# WizBoard.net
KiCad netlist of a schematic drawn in Altium Designer
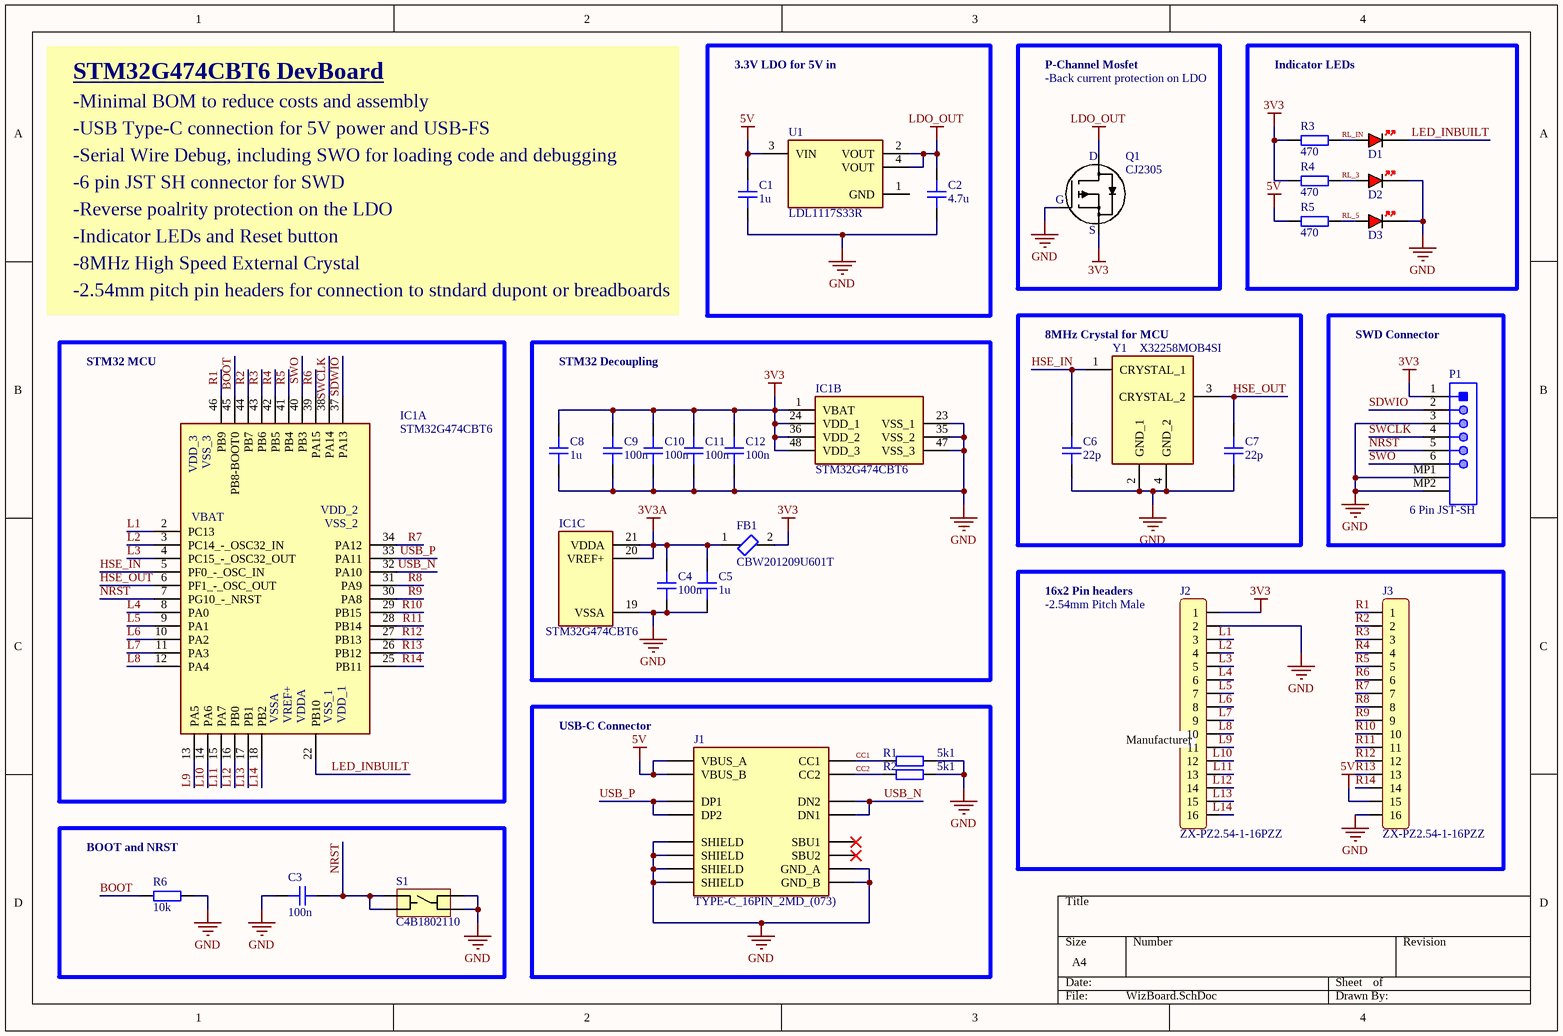
[diagram p0: WizBoard.SchDoc]

(export (version "E")
  (design (tool "Eeschema 10.0.6"))
  (components
    (comp (ref "C1")
      (value "1u")
      (footprint "CAP_0805")
      (description "Capacitor SMD 0805")
      (fields
        (field (name "MANUFACTURER") "Samsung Electro-Mechanics")
        (field (name "MANUFACTURER PART NUMBER") "CL21B105KAFNNNE")
      )
      (libsource (lib "BRye_SCHLib") (part "CAP_0805"))
    )
    (comp (ref "C2")
      (value "4.7u")
      (footprint "CAP_0805")
      (description "Capacitor SMD 0805")
      (fields
        (field (name "MANUFACTURER") "Samsung Electro-Mechanics")
        (field (name "MANUFACTURER PART NUMBER") "CL21A475KBQNNNE")
      )
      (libsource (lib "BRye_SCHLib") (part "CAP_0805"))
    )
    (comp (ref "C3")
      (value "100n")
      (footprint "CAP_0805")
      (description "Capacitor SMD 0805")
      (fields
        (field (name "MANUFACTURER") "Samsung Electro-Mechanics")
        (field (name "MANUFACTURER PART NUMBER") "CL21B104KBCNNNC")
      )
      (libsource (lib "BRye_SCHLib") (part "CAP_0805"))
    )
    (comp (ref "C4")
      (value "100n")
      (footprint "CAP_0805")
      (description "Capacitor SMD 0805")
      (fields
        (field (name "MANUFACTURER") "Samsung Electro-Mechanics")
        (field (name "MANUFACTURER PART NUMBER") "CL21B104KBCNNNC")
      )
      (libsource (lib "BRye_SCHLib") (part "CAP_0805"))
    )
    (comp (ref "C5")
      (value "1u")
      (footprint "CAP_0805")
      (description "Capacitor SMD 0805")
      (fields
        (field (name "MANUFACTURER") "Samsung Electro-Mechanics")
        (field (name "MANUFACTURER PART NUMBER") "CL21B105KAFNNNE")
      )
      (libsource (lib "BRye_SCHLib") (part "CAP_0805"))
    )
    (comp (ref "C6")
      (value "22p")
      (footprint "CAP_0805")
      (description "Capacitor SMD 0805")
      (fields
        (field (name "MANUFACTURER") "Samsung Electro-Mechanics")
        (field (name "MANUFACTURER PART NUMBER") "CL21C220JBANNNC")
      )
      (libsource (lib "BRye_SCHLib") (part "CAP_0805"))
    )
    (comp (ref "C7")
      (value "22p")
      (footprint "CAP_0805")
      (description "Capacitor SMD 0805")
      (fields
        (field (name "MANUFACTURER") "Samsung Electro-Mechanics")
        (field (name "MANUFACTURER PART NUMBER") "CL21C220JBANNNC")
      )
      (libsource (lib "BRye_SCHLib") (part "CAP_0805"))
    )
    (comp (ref "C8")
      (value "1u")
      (footprint "CAP_0805")
      (description "Capacitor SMD 0805")
      (fields
        (field (name "MANUFACTURER") "Samsung Electro-Mechanics")
        (field (name "MANUFACTURER PART NUMBER") "CL21B105KAFNNNE")
      )
      (libsource (lib "BRye_SCHLib") (part "CAP_0805"))
    )
    (comp (ref "C9")
      (value "100n")
      (footprint "CAP_0805")
      (description "Capacitor SMD 0805")
      (fields
        (field (name "MANUFACTURER") "Samsung Electro-Mechanics")
        (field (name "MANUFACTURER PART NUMBER") "CL21B104KBCNNNC")
      )
      (libsource (lib "BRye_SCHLib") (part "CAP_0805"))
    )
    (comp (ref "C10")
      (value "100n")
      (footprint "CAP_0805")
      (description "Capacitor SMD 0805")
      (fields
        (field (name "MANUFACTURER") "Samsung Electro-Mechanics")
        (field (name "MANUFACTURER PART NUMBER") "CL21B104KBCNNNC")
      )
      (libsource (lib "BRye_SCHLib") (part "CAP_0805"))
    )
    (comp (ref "C11")
      (value "100n")
      (footprint "CAP_0805")
      (description "Capacitor SMD 0805")
      (fields
        (field (name "MANUFACTURER") "Samsung Electro-Mechanics")
        (field (name "MANUFACTURER PART NUMBER") "CL21B104KBCNNNC")
      )
      (libsource (lib "BRye_SCHLib") (part "CAP_0805"))
    )
    (comp (ref "C12")
      (value "100n")
      (footprint "CAP_0805")
      (description "Capacitor SMD 0805")
      (fields
        (field (name "MANUFACTURER") "Samsung Electro-Mechanics")
        (field (name "MANUFACTURER PART NUMBER") "CL21B104KBCNNNC")
      )
      (libsource (lib "BRye_SCHLib") (part "CAP_0805"))
    )
    (comp (ref "D1")
      (value "RED")
      (footprint "LED_0805_RED")
      (description "LED 0805 RED SMD")
      (fields
        (field (name "MANUFACTURER") "XINGLIGHT")
        (field (name "MANUFACTURER PART NUMBER") "XL-2012SURC")
      )
      (libsource (lib "BRye_SCHLib") (part "LED_0805_RED"))
    )
    (comp (ref "D2")
      (value "RED")
      (footprint "LED_0805_RED")
      (description "LED 0805 RED SMD")
      (fields
        (field (name "MANUFACTURER") "XINGLIGHT")
        (field (name "MANUFACTURER PART NUMBER") "XL-2012SURC")
      )
      (libsource (lib "BRye_SCHLib") (part "LED_0805_RED"))
    )
    (comp (ref "D3")
      (value "RED")
      (footprint "LED_0805_RED")
      (description "LED 0805 RED SMD")
      (fields
        (field (name "MANUFACTURER") "XINGLIGHT")
        (field (name "MANUFACTURER PART NUMBER") "XL-2012SURC")
      )
      (libsource (lib "BRye_SCHLib") (part "LED_0805_RED"))
    )
    (comp (ref "FB1")
      (value "CBW201209U601T")
      (footprint "SamacSys:BEADC2112X105N")
      (description "Ferrite Beads 600 @ 100MHz 500mA 0805 RoHS")
      (fields (field (name "MANUFACTURER") "SUNLORD"))
      (libsource (lib "BRye_SCHLib") (part "GZ2012D601TF"))
    )
    (comp (ref "IC1")
      (value "STM32G474CBT6")
      (footprint "SamacSys:QFP50P900X900X160-48N")
      (description "Integrated Circuit")
      (fields
        (field (name "MANUFACTURER") "STMicroelectronics")
        (field (name "MANUFACTURER PART NUMBER") "STM32G474CBT6TR")
      )
      (libsource (lib "BRye_SCHLib") (part "STM32G474CBT6"))
    )
    (comp (ref "J1")
      (value "TYPE-C_16PIN_2MD_(073)")
      (footprint "SHOUHAN_TYPE-C_16PIN_2MD_(073)")
      (description "DC-5V 5A Type C USB")
      (fields
        (field (name "MANUFACTURER") "SHOU HAN")
        (field (name "MANUFACTURER PART NUMBER") "TYPE-C 16PIN 2MD(073)")
      )
      (libsource (lib "BRye_SCHLib") (part "TYPE-C_16PIN_2MD_(073)"))
    )
    (comp (ref "J2")
      (value "ZX-PZ2.54-1-16PZZ")
      (footprint "16p Pin Header")
      (fields (field (name "MANUFACTURER") "Megastar"))
      (libsource (lib "BRye_SCHLib") (part "ZX-PZ2.54-1-16PZZ"))
    )
    (comp (ref "J3")
      (value "ZX-PZ2.54-1-16PZZ")
      (footprint "16p Pin Header")
      (fields (field (name "MANUFACTURER") "Megastar"))
      (libsource (lib "BRye_SCHLib") (part "ZX-PZ2.54-1-16PZZ"))
    )
    (comp (ref "P1")
      (value "6 Pin JST-SH")
      (footprint "JST-SM06B-SRSS-TB_V")
      (description "Male Header, Pitch 1 mm, 1 x 6 Position, Height 2.95 mm, -25 to 85 degC, RoHS, Tape and Reel")
      (fields
        (field (name "MANUFACTURER") "JST")
        (field (name "MANUFACTURER PART NUMBER") "SM06B-SRSS-TB(LF)(SN)")
      )
      (libsource (lib "Altium Content Vault") (part "CN-1P-2M-R6"))
    )
    (comp (ref "Q1")
      (value "CJ2305")
      (footprint "SOT-23")
      (description "P-Channel 12V 4.1A 0.35W Surface Mount SOT-23")
      (fields (field (name "MANUFACTURER") "JSCJ"))
      (libsource (lib "BRye_SCHLib") (part "PJM10H01PSA"))
    )
    (comp (ref "R1")
      (value "5k1")
      (footprint "RES_0805")
      (description "Resistor SMD 0805")
      (fields
        (field (name "MANUFACTURER") "FOJAN")
        (field (name "MANUFACTURER PART NUMBER") "FRC0805F5101TS")
      )
      (libsource (lib "BRye_SCHLib") (part "RES_0805"))
    )
    (comp (ref "R2")
      (value "5k1")
      (footprint "RES_0805")
      (description "Resistor SMD 0805")
      (fields
        (field (name "MANUFACTURER") "FOJAN")
        (field (name "MANUFACTURER PART NUMBER") "FRC0805F5101TS")
      )
      (libsource (lib "BRye_SCHLib") (part "RES_0805"))
    )
    (comp (ref "R3")
      (value "470")
      (footprint "RES_0805")
      (description "Resistor SMD 0805")
      (fields
        (field (name "MANUFACTURER") "FOJAN")
        (field (name "MANUFACTURER PART NUMBER") "FRC0805F4700TS")
      )
      (libsource (lib "BRye_SCHLib") (part "RES_0805"))
    )
    (comp (ref "R4")
      (value "470")
      (footprint "RES_0805")
      (description "Resistor SMD 0805")
      (fields
        (field (name "MANUFACTURER") "FOJAN")
        (field (name "MANUFACTURER PART NUMBER") "FRC0805F4700TS")
      )
      (libsource (lib "BRye_SCHLib") (part "RES_0805"))
    )
    (comp (ref "R5")
      (value "470")
      (footprint "RES_0805")
      (description "Resistor SMD 0805")
      (fields
        (field (name "MANUFACTURER") "FOJAN")
        (field (name "MANUFACTURER PART NUMBER") "FRC0805F4700TS")
      )
      (libsource (lib "BRye_SCHLib") (part "RES_0805"))
    )
    (comp (ref "R6")
      (value "10k")
      (footprint "RES_0805")
      (description "Resistor SMD 0805")
      (fields
        (field (name "MANUFACTURER") "FOJAN")
        (field (name "MANUFACTURER PART NUMBER") "FRC0805F1002TS")
      )
      (libsource (lib "BRye_SCHLib") (part "RES_0805"))
    )
    (comp (ref "S1")
      (value "C4B1802110")
      (footprint "SW-SMD_4P-L3.5-W3.0-P1.50-LS4.7")
      (description "SMD NO Push Button Switch")
      (fields (field (name "MANUFACTURER") "SAMZO"))
      (libsource (lib "BRye_SCHLib") (part "C4B1802110"))
    )
    (comp (ref "U1")
      (value "LDL1117S33R")
      (footprint "SOT-223")
      (description "IC REG LINEAR 3.3V 1.2A SOT223")
      (fields (field (name "MANUFACTURER") "ST"))
      (libsource (lib "BRye_SCHLib") (part "LDL1117S33R"))
    )
    (comp (ref "Y1")
      (value "X32258MOB4SI")
      (footprint "SamacSys:X32258MOB4SI")
      (description "Crystal or Oscillator")
      (fields (field (name "MANUFACTURER") "YXC"))
      (libsource (lib "BRye_SCHLib") (part "X32258MOB4SI"))
    )
  )
  (nets
    (net (code "1") (name "/BOOT") (class "Default")
      (node (ref "IC1") (pin "45") (pinfunction "PB8-BOOT0_45") (pintype "passive"))
      (node (ref "R6") (pin "1") (pinfunction "1_1") (pintype "passive"))
    )
    (net (code "2") (name "/CC1") (class "Default")
      (node (ref "J1") (pin "A5") (pinfunction "CC1_A5") (pintype "passive"))
      (node (ref "R1") (pin "1") (pinfunction "1_1") (pintype "passive"))
    )
    (net (code "3") (name "/CC2") (class "Default")
      (node (ref "J1") (pin "B5") (pinfunction "CC2_B5") (pintype "passive"))
      (node (ref "R2") (pin "1") (pinfunction "1_1") (pintype "passive"))
    )
    (net (code "4") (name "/HSE_IN") (class "Default")
      (node (ref "C6") (pin "2") (pinfunction "2_2") (pintype "passive"))
      (node (ref "IC1") (pin "5") (pinfunction "PF0_-_OSC_IN_5") (pintype "passive"))
      (node (ref "Y1") (pin "1") (pinfunction "CRYSTAL_1_1") (pintype "passive"))
    )
    (net (code "5") (name "/HSE_OUT") (class "Default")
      (node (ref "C7") (pin "2") (pinfunction "2_2") (pintype "passive"))
      (node (ref "IC1") (pin "6") (pinfunction "PF1_-_OSC_OUT_6") (pintype "passive"))
      (node (ref "Y1") (pin "3") (pinfunction "CRYSTAL_2_3") (pintype "passive"))
    )
    (net (code "6") (name "/L1") (class "Default")
      (node (ref "IC1") (pin "2") (pinfunction "PC13_2") (pintype "passive"))
      (node (ref "J2") (pin "3") (pinfunction "3_3") (pintype "passive"))
    )
    (net (code "7") (name "/L2") (class "Default")
      (node (ref "IC1") (pin "3") (pinfunction "PC14_-_OSC32_IN_3") (pintype "passive"))
      (node (ref "J2") (pin "4") (pinfunction "4_4") (pintype "passive"))
    )
    (net (code "8") (name "/L3") (class "Default")
      (node (ref "IC1") (pin "4") (pinfunction "PC15_-_OSC32_OUT_4") (pintype "passive"))
      (node (ref "J2") (pin "5") (pinfunction "5_5") (pintype "passive"))
    )
    (net (code "9") (name "/L4") (class "Default")
      (node (ref "IC1") (pin "8") (pinfunction "PA0_8") (pintype "passive"))
      (node (ref "J2") (pin "6") (pinfunction "6_6") (pintype "passive"))
    )
    (net (code "10") (name "/L5") (class "Default")
      (node (ref "IC1") (pin "9") (pinfunction "PA1_9") (pintype "passive"))
      (node (ref "J2") (pin "7") (pinfunction "7_7") (pintype "passive"))
    )
    (net (code "11") (name "/L6") (class "Default")
      (node (ref "IC1") (pin "10") (pinfunction "PA2_10") (pintype "passive"))
      (node (ref "J2") (pin "8") (pinfunction "8_8") (pintype "passive"))
    )
    (net (code "12") (name "/L7") (class "Default")
      (node (ref "IC1") (pin "11") (pinfunction "PA3_11") (pintype "passive"))
      (node (ref "J2") (pin "9") (pinfunction "9_9") (pintype "passive"))
    )
    (net (code "13") (name "/L8") (class "Default")
      (node (ref "IC1") (pin "12") (pinfunction "PA4_12") (pintype "passive"))
      (node (ref "J2") (pin "10") (pinfunction "10_10") (pintype "passive"))
    )
    (net (code "14") (name "/L9") (class "Default")
      (node (ref "IC1") (pin "13") (pinfunction "PA5_13") (pintype "passive"))
      (node (ref "J2") (pin "11") (pinfunction "11_11") (pintype "passive"))
    )
    (net (code "15") (name "/L10") (class "Default")
      (node (ref "IC1") (pin "14") (pinfunction "PA6_14") (pintype "passive"))
      (node (ref "J2") (pin "12") (pinfunction "12_12") (pintype "passive"))
    )
    (net (code "16") (name "/L11") (class "Default")
      (node (ref "IC1") (pin "15") (pinfunction "PA7_15") (pintype "passive"))
      (node (ref "J2") (pin "13") (pinfunction "13_13") (pintype "passive"))
    )
    (net (code "17") (name "/L12") (class "Default")
      (node (ref "IC1") (pin "16") (pinfunction "PB0_16") (pintype "passive"))
      (node (ref "J2") (pin "14") (pinfunction "14_14") (pintype "passive"))
    )
    (net (code "18") (name "/L13") (class "Default")
      (node (ref "IC1") (pin "17") (pinfunction "PB1_17") (pintype "passive"))
      (node (ref "J2") (pin "15") (pinfunction "15_15") (pintype "passive"))
    )
    (net (code "19") (name "/L14") (class "Default")
      (node (ref "IC1") (pin "18") (pinfunction "PB2_18") (pintype "passive"))
      (node (ref "J2") (pin "16") (pinfunction "16_16") (pintype "passive"))
    )
    (net (code "20") (name "/LED_INBUILT") (class "Default")
      (node (ref "D1") (pin "K") (pinfunction "K_K") (pintype "passive"))
      (node (ref "IC1") (pin "22") (pinfunction "PB10_22") (pintype "passive"))
    )
    (net (code "21") (name "/NRST") (class "Default")
      (node (ref "C3") (pin "1") (pinfunction "1_1") (pintype "passive"))
      (node (ref "IC1") (pin "7") (pinfunction "PG10_-_NRST_7") (pintype "passive"))
      (node (ref "P1") (pin "5") (pinfunction "5_5") (pintype "passive"))
      (node (ref "S1") (pin "1") (pinfunction "1_1") (pintype "passive"))
      (node (ref "S1") (pin "2") (pinfunction "2_2") (pintype "passive"))
    )
    (net (code "22") (name "/R1") (class "Default")
      (node (ref "IC1") (pin "46") (pinfunction "PB9_46") (pintype "passive"))
      (node (ref "J3") (pin "1") (pinfunction "1_1") (pintype "passive"))
    )
    (net (code "23") (name "/R2") (class "Default")
      (node (ref "IC1") (pin "44") (pinfunction "PB7_44") (pintype "passive"))
      (node (ref "J3") (pin "2") (pinfunction "2_2") (pintype "passive"))
    )
    (net (code "24") (name "/R3") (class "Default")
      (node (ref "IC1") (pin "43") (pinfunction "PB6_43") (pintype "passive"))
      (node (ref "J3") (pin "3") (pinfunction "3_3") (pintype "passive"))
    )
    (net (code "25") (name "/R4") (class "Default")
      (node (ref "IC1") (pin "42") (pinfunction "PB5_42") (pintype "passive"))
      (node (ref "J3") (pin "4") (pinfunction "4_4") (pintype "passive"))
    )
    (net (code "26") (name "/R5") (class "Default")
      (node (ref "IC1") (pin "41") (pinfunction "PB4_41") (pintype "passive"))
      (node (ref "J3") (pin "5") (pinfunction "5_5") (pintype "passive"))
    )
    (net (code "27") (name "/R6") (class "Default")
      (node (ref "IC1") (pin "39") (pinfunction "PA15_39") (pintype "passive"))
      (node (ref "J3") (pin "6") (pinfunction "6_6") (pintype "passive"))
    )
    (net (code "28") (name "/R7") (class "Default")
      (node (ref "IC1") (pin "34") (pinfunction "PA12_34") (pintype "passive"))
      (node (ref "J3") (pin "7") (pinfunction "7_7") (pintype "passive"))
    )
    (net (code "29") (name "/R8") (class "Default")
      (node (ref "IC1") (pin "31") (pinfunction "PA9_31") (pintype "passive"))
      (node (ref "J3") (pin "8") (pinfunction "8_8") (pintype "passive"))
    )
    (net (code "30") (name "/R9") (class "Default")
      (node (ref "IC1") (pin "30") (pinfunction "PA8_30") (pintype "passive"))
      (node (ref "J3") (pin "9") (pinfunction "9_9") (pintype "passive"))
    )
    (net (code "31") (name "/R10") (class "Default")
      (node (ref "IC1") (pin "29") (pinfunction "PB15_29") (pintype "passive"))
      (node (ref "J3") (pin "10") (pinfunction "10_10") (pintype "passive"))
    )
    (net (code "32") (name "/R11") (class "Default")
      (node (ref "IC1") (pin "28") (pinfunction "PB14_28") (pintype "passive"))
      (node (ref "J3") (pin "11") (pinfunction "11_11") (pintype "passive"))
    )
    (net (code "33") (name "/R12") (class "Default")
      (node (ref "IC1") (pin "27") (pinfunction "PB13_27") (pintype "passive"))
      (node (ref "J3") (pin "12") (pinfunction "12_12") (pintype "passive"))
    )
    (net (code "34") (name "/R13") (class "Default")
      (node (ref "IC1") (pin "26") (pinfunction "PB12_26") (pintype "passive"))
      (node (ref "J3") (pin "13") (pinfunction "13_13") (pintype "passive"))
    )
    (net (code "35") (name "/R14") (class "Default")
      (node (ref "IC1") (pin "25") (pinfunction "PB11_25") (pintype "passive"))
      (node (ref "J3") (pin "14") (pinfunction "14_14") (pintype "passive"))
    )
    (net (code "36") (name "/RL_3") (class "Default")
      (node (ref "D2") (pin "A") (pinfunction "A_A") (pintype "passive"))
      (node (ref "R4") (pin "2") (pinfunction "2_2") (pintype "passive"))
    )
    (net (code "37") (name "/RL_5") (class "Default")
      (node (ref "D3") (pin "A") (pinfunction "A_A") (pintype "passive"))
      (node (ref "R5") (pin "2") (pinfunction "2_2") (pintype "passive"))
    )
    (net (code "38") (name "/RL_IN") (class "Default")
      (node (ref "D1") (pin "A") (pinfunction "A_A") (pintype "passive"))
      (node (ref "R3") (pin "2") (pinfunction "2_2") (pintype "passive"))
    )
    (net (code "39") (name "/SDWIO") (class "Default")
      (node (ref "IC1") (pin "37") (pinfunction "PA13_37") (pintype "passive"))
      (node (ref "P1") (pin "2") (pinfunction "2_2") (pintype "passive"))
    )
    (net (code "40") (name "/SWCLK") (class "Default")
      (node (ref "IC1") (pin "38") (pinfunction "PA14_38") (pintype "passive"))
      (node (ref "P1") (pin "4") (pinfunction "4_4") (pintype "passive"))
    )
    (net (code "41") (name "/SWO") (class "Default")
      (node (ref "IC1") (pin "40") (pinfunction "PB3_40") (pintype "passive"))
      (node (ref "P1") (pin "6") (pinfunction "6_6") (pintype "passive"))
    )
    (net (code "42") (name "/USB_N") (class "Default")
      (node (ref "IC1") (pin "32") (pinfunction "PA10_32") (pintype "passive"))
      (node (ref "J1") (pin "A7") (pinfunction "DN1_A7") (pintype "passive"))
      (node (ref "J1") (pin "B7") (pinfunction "DN2_B7") (pintype "passive"))
    )
    (net (code "43") (name "/USB_P") (class "Default")
      (node (ref "IC1") (pin "33") (pinfunction "PA11_33") (pintype "passive"))
      (node (ref "J1") (pin "A6") (pinfunction "DP1_A6") (pintype "passive"))
      (node (ref "J1") (pin "B6") (pinfunction "DP2_B6") (pintype "passive"))
    )
    (net (code "44") (name "3V3") (class "Default")
      (node (ref "C10") (pin "2") (pinfunction "2_2") (pintype "passive"))
      (node (ref "C11") (pin "2") (pinfunction "2_2") (pintype "passive"))
      (node (ref "C12") (pin "2") (pinfunction "2_2") (pintype "passive"))
      (node (ref "C8") (pin "2") (pinfunction "2_2") (pintype "passive"))
      (node (ref "C9") (pin "2") (pinfunction "2_2") (pintype "passive"))
      (node (ref "FB1") (pin "2") (pinfunction "2_2") (pintype "passive"))
      (node (ref "IC1") (pin "1") (pinfunction "VBAT_1") (pintype "passive"))
      (node (ref "IC1") (pin "24") (pinfunction "VDD_1_24") (pintype "passive"))
      (node (ref "IC1") (pin "36") (pinfunction "VDD_2_36") (pintype "passive"))
      (node (ref "IC1") (pin "48") (pinfunction "VDD_3_48") (pintype "passive"))
      (node (ref "J2") (pin "1") (pinfunction "1_1") (pintype "passive"))
      (node (ref "P1") (pin "1") (pinfunction "1_1") (pintype "passive"))
      (node (ref "Q1") (pin "2") (pinfunction "Source_2") (pintype "passive"))
      (node (ref "R3") (pin "1") (pinfunction "1_1") (pintype "passive"))
      (node (ref "R4") (pin "1") (pinfunction "1_1") (pintype "passive"))
    )
    (net (code "45") (name "3V3A") (class "Default")
      (node (ref "C4") (pin "2") (pinfunction "2_2") (pintype "passive"))
      (node (ref "C5") (pin "2") (pinfunction "2_2") (pintype "passive"))
      (node (ref "FB1") (pin "1") (pinfunction "1_1") (pintype "passive"))
      (node (ref "IC1") (pin "20") (pinfunction "VREF+_20") (pintype "passive"))
      (node (ref "IC1") (pin "21") (pinfunction "VDDA_21") (pintype "passive"))
    )
    (net (code "46") (name "5V") (class "Default")
      (node (ref "C1") (pin "2") (pinfunction "2_2") (pintype "passive"))
      (node (ref "J1") (pin "A4_B9") (pinfunction "VBUS_A_A4_B9") (pintype "passive"))
      (node (ref "J1") (pin "B4_A9") (pinfunction "VBUS_B_B4_A9") (pintype "passive"))
      (node (ref "J3") (pin "15") (pinfunction "15_15") (pintype "passive"))
      (node (ref "R5") (pin "1") (pinfunction "1_1") (pintype "passive"))
      (node (ref "U1") (pin "3") (pinfunction "VIN_3") (pintype "power_in"))
    )
    (net (code "47") (name "GND") (class "Default")
      (node (ref "C1") (pin "1") (pinfunction "1_1") (pintype "passive"))
      (node (ref "C10") (pin "1") (pinfunction "1_1") (pintype "passive"))
      (node (ref "C11") (pin "1") (pinfunction "1_1") (pintype "passive"))
      (node (ref "C12") (pin "1") (pinfunction "1_1") (pintype "passive"))
      (node (ref "C2") (pin "1") (pinfunction "1_1") (pintype "passive"))
      (node (ref "C3") (pin "2") (pinfunction "2_2") (pintype "passive"))
      (node (ref "C4") (pin "1") (pinfunction "1_1") (pintype "passive"))
      (node (ref "C5") (pin "1") (pinfunction "1_1") (pintype "passive"))
      (node (ref "C6") (pin "1") (pinfunction "1_1") (pintype "passive"))
      (node (ref "C7") (pin "1") (pinfunction "1_1") (pintype "passive"))
      (node (ref "C8") (pin "1") (pinfunction "1_1") (pintype "passive"))
      (node (ref "C9") (pin "1") (pinfunction "1_1") (pintype "passive"))
      (node (ref "D2") (pin "K") (pinfunction "K_K") (pintype "passive"))
      (node (ref "D3") (pin "K") (pinfunction "K_K") (pintype "passive"))
      (node (ref "IC1") (pin "19") (pinfunction "VSSA_19") (pintype "passive"))
      (node (ref "IC1") (pin "23") (pinfunction "VSS_1_23") (pintype "passive"))
      (node (ref "IC1") (pin "35") (pinfunction "VSS_2_35") (pintype "passive"))
      (node (ref "IC1") (pin "47") (pinfunction "VSS_3_47") (pintype "passive"))
      (node (ref "J1") (pin "A1_B12") (pinfunction "GND_A_A1_B12") (pintype "passive"))
      (node (ref "J1") (pin "B1_A12") (pinfunction "GND_B_B1_A12") (pintype "passive"))
      (node (ref "J1") (pin "SH1") (pinfunction "SHIELD_SH1") (pintype "passive"))
      (node (ref "J1") (pin "SH2") (pinfunction "SHIELD_SH2") (pintype "passive"))
      (node (ref "J1") (pin "SH3") (pinfunction "SHIELD_SH3") (pintype "passive"))
      (node (ref "J1") (pin "SH4") (pinfunction "SHIELD_SH4") (pintype "passive"))
      (node (ref "J2") (pin "2") (pinfunction "2_2") (pintype "passive"))
      (node (ref "J3") (pin "16") (pinfunction "16_16") (pintype "passive"))
      (node (ref "P1") (pin "3") (pinfunction "3_3") (pintype "passive"))
      (node (ref "P1") (pin "MP1") (pinfunction "MP1_MP1") (pintype "passive"))
      (node (ref "P1") (pin "MP2") (pinfunction "MP2_MP2") (pintype "passive"))
      (node (ref "Q1") (pin "1") (pinfunction "Gate_1") (pintype "passive"))
      (node (ref "R1") (pin "2") (pinfunction "2_2") (pintype "passive"))
      (node (ref "R2") (pin "2") (pinfunction "2_2") (pintype "passive"))
      (node (ref "R6") (pin "2") (pinfunction "2_2") (pintype "passive"))
      (node (ref "S1") (pin "3") (pinfunction "3_3") (pintype "passive"))
      (node (ref "S1") (pin "4") (pinfunction "4_4") (pintype "passive"))
      (node (ref "Y1") (pin "2") (pinfunction "GND_1_2") (pintype "passive"))
      (node (ref "Y1") (pin "4") (pinfunction "GND_2_4") (pintype "passive"))
    )
    (net (code "48") (name "LDO_OUT") (class "Default")
      (node (ref "C2") (pin "2") (pinfunction "2_2") (pintype "passive"))
      (node (ref "Q1") (pin "3") (pinfunction "Drain_3") (pintype "passive"))
      (node (ref "U1") (pin "2") (pinfunction "VOUT_2") (pintype "passive"))
      (node (ref "U1") (pin "4") (pinfunction "VOUT_4") (pintype "passive"))
    )
    (net (code "49") (name "unconnected-(J1-SBU1-PadA8)") (class "Default")
      (node (ref "J1") (pin "A8") (pinfunction "SBU1_A8") (pintype "passive+no_connect"))
    )
    (net (code "50") (name "unconnected-(J1-SBU2-PadB8)") (class "Default")
      (node (ref "J1") (pin "B8") (pinfunction "SBU2_B8") (pintype "passive+no_connect"))
    )
    (net (code "51") (name "unconnected-(U1-GND-Pad1)") (class "Default")
      (node (ref "U1") (pin "1") (pinfunction "GND_1") (pintype "power_in"))
    )
  )
)
